# SCH_spacedrums_Altium.net
KiCad netlist of a schematic drawn in Altium Designer
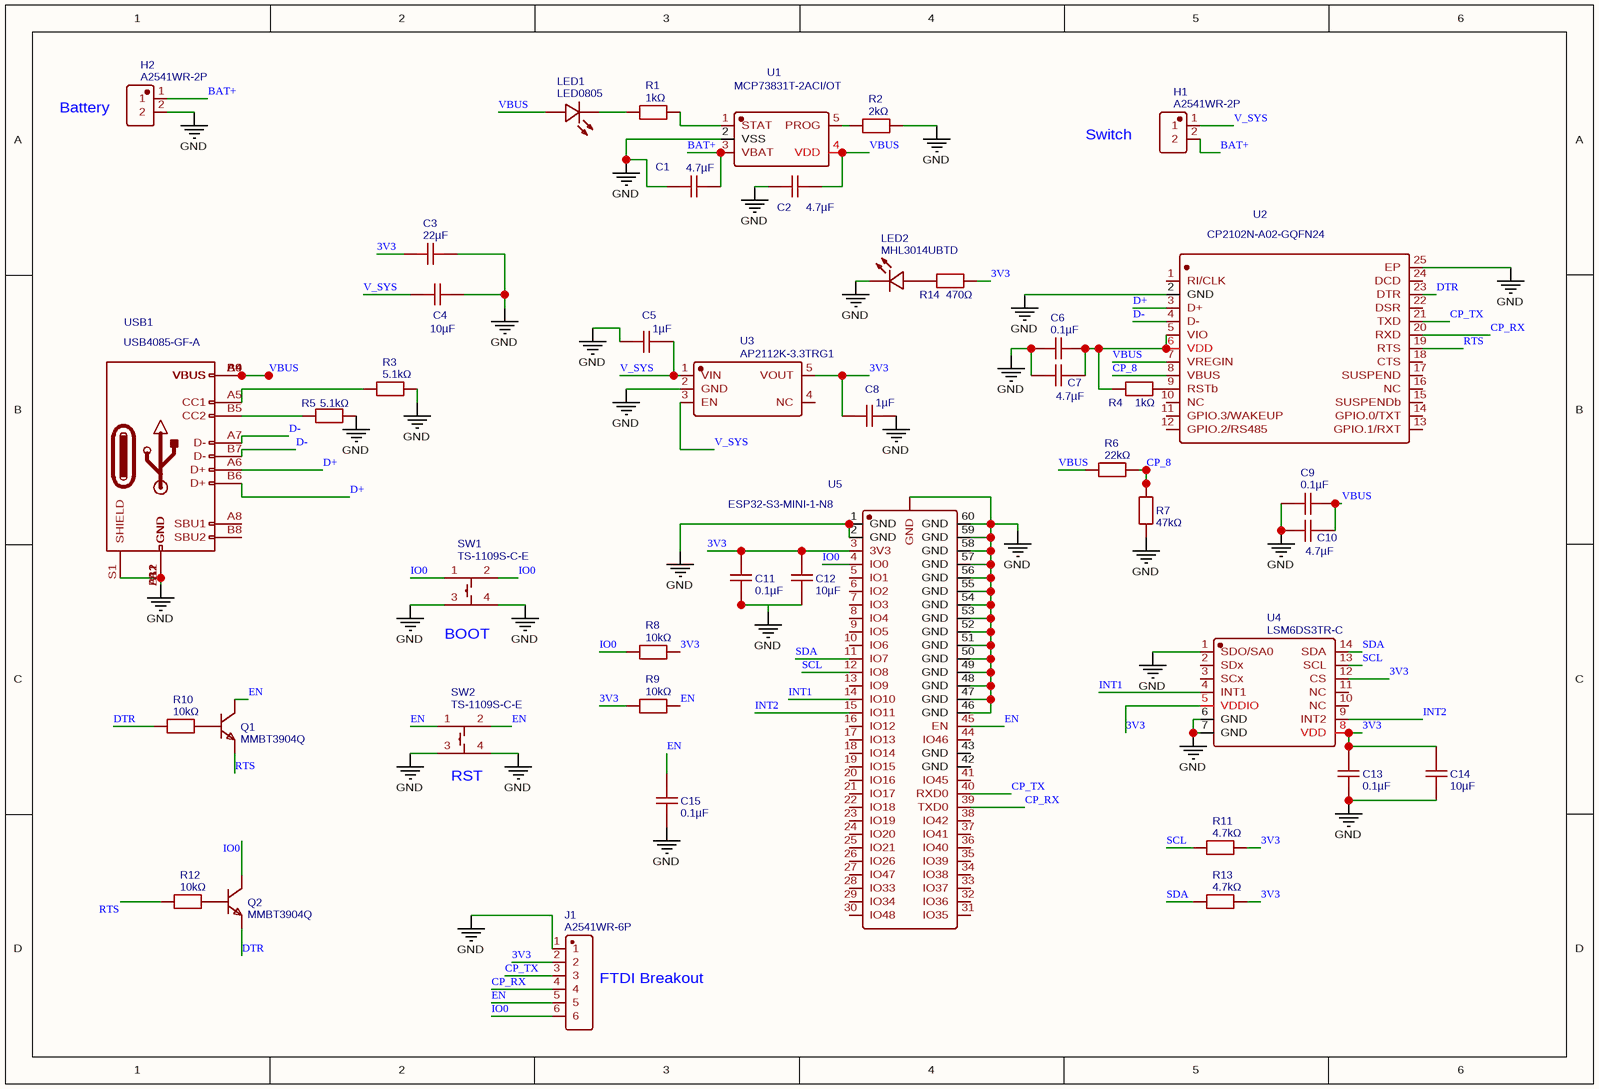
[diagram p0: SCH_spacedrums_Altium.schdoc]

(export (version "E")
  (design (tool "Eeschema 10.0.6"))
  (components
    (comp (ref "C1")
      (value "4.7µF")
      (fields
        (field (name "MANUFACTURER") "YAGEO(国巨)")
        (field (name "MANUFACTURER PART") "CC0805FRNPO0BN680")
        (field (name "CONTRIBUTOR") "lcsc")
      )
      (libsource (lib "altium-import") (part "root_0_4.7µF_"))
    )
    (comp (ref "C2")
      (value "4.7µF")
      (fields
        (field (name "MANUFACTURER") "YAGEO(国巨)")
        (field (name "MANUFACTURER PART") "CC0805FRNPO0BN680")
        (field (name "CONTRIBUTOR") "lcsc")
      )
      (libsource (lib "altium-import") (part "root_0_4.7µF_"))
    )
    (comp (ref "C3")
      (value "22µF")
      (fields
        (field (name "MANUFACTURER") "YAGEO(国巨)")
        (field (name "MANUFACTURER PART") "CC0805FRNPO0BN680")
        (field (name "CONTRIBUTOR") "lcsc")
      )
      (libsource (lib "altium-import") (part "root_0_22µF_"))
    )
    (comp (ref "C4")
      (value "10µF")
      (fields
        (field (name "MANUFACTURER") "YAGEO(国巨)")
        (field (name "MANUFACTURER PART") "CC0805FRNPO0BN680")
        (field (name "CONTRIBUTOR") "lcsc")
      )
      (libsource (lib "altium-import") (part "root_0_10µF_"))
    )
    (comp (ref "C5")
      (value "1µF")
      (fields
        (field (name "MANUFACTURER") "YAGEO(国巨)")
        (field (name "MANUFACTURER PART") "CC0805FRNPO0BN680")
        (field (name "CONTRIBUTOR") "lcsc")
      )
      (libsource (lib "altium-import") (part "root_0_1µF_"))
    )
    (comp (ref "C6")
      (value "0.1µF")
      (fields
        (field (name "MANUFACTURER") "YAGEO(国巨)")
        (field (name "MANUFACTURER PART") "CC0805FRNPO0BN680")
        (field (name "CONTRIBUTOR") "lcsc")
      )
      (libsource (lib "altium-import") (part "root_0_0.1µF_"))
    )
    (comp (ref "C7")
      (value "4.7µF")
      (fields
        (field (name "MANUFACTURER") "YAGEO(国巨)")
        (field (name "MANUFACTURER PART") "CC0805FRNPO0BN680")
        (field (name "CONTRIBUTOR") "lcsc")
      )
      (libsource (lib "altium-import") (part "root_0_4.7µF_"))
    )
    (comp (ref "C8")
      (value "1µF")
      (fields
        (field (name "MANUFACTURER") "YAGEO(国巨)")
        (field (name "MANUFACTURER PART") "CC0805FRNPO0BN680")
        (field (name "CONTRIBUTOR") "lcsc")
      )
      (libsource (lib "altium-import") (part "root_0_1µF_"))
    )
    (comp (ref "C9")
      (value "0.1µF")
      (fields
        (field (name "MANUFACTURER") "YAGEO(国巨)")
        (field (name "MANUFACTURER PART") "CC0805FRNPO0BN680")
        (field (name "CONTRIBUTOR") "lcsc")
      )
      (libsource (lib "altium-import") (part "root_0_0.1µF_"))
    )
    (comp (ref "C10")
      (value "4.7µF")
      (fields
        (field (name "MANUFACTURER") "YAGEO(国巨)")
        (field (name "MANUFACTURER PART") "CC0805FRNPO0BN680")
        (field (name "CONTRIBUTOR") "lcsc")
      )
      (libsource (lib "altium-import") (part "root_0_4.7µF_"))
    )
    (comp (ref "C11")
      (value "0.1µF")
      (fields
        (field (name "MANUFACTURER") "YAGEO(国巨)")
        (field (name "MANUFACTURER PART") "CC0805FRNPO0BN680")
        (field (name "CONTRIBUTOR") "lcsc")
      )
      (libsource (lib "altium-import") (part "root_1_0.1µF_"))
    )
    (comp (ref "C12")
      (value "10µF")
      (fields
        (field (name "MANUFACTURER") "YAGEO(国巨)")
        (field (name "MANUFACTURER PART") "CC0805FRNPO0BN680")
        (field (name "CONTRIBUTOR") "lcsc")
      )
      (libsource (lib "altium-import") (part "root_1_10µF_"))
    )
    (comp (ref "C13")
      (value "0.1µF")
      (fields
        (field (name "MANUFACTURER") "YAGEO(国巨)")
        (field (name "MANUFACTURER PART") "CC0805FRNPO0BN680")
        (field (name "CONTRIBUTOR") "lcsc")
      )
      (libsource (lib "altium-import") (part "root_1_0.1µF_"))
    )
    (comp (ref "C14")
      (value "10µF")
      (fields
        (field (name "MANUFACTURER") "YAGEO(国巨)")
        (field (name "MANUFACTURER PART") "CC0805FRNPO0BN680")
        (field (name "CONTRIBUTOR") "lcsc")
      )
      (libsource (lib "altium-import") (part "root_1_10µF_"))
    )
    (comp (ref "C15")
      (value "0.1µF")
      (fields
        (field (name "MANUFACTURER") "YAGEO(国巨)")
        (field (name "MANUFACTURER PART") "CC0805FRNPO0BN680")
        (field (name "CONTRIBUTOR") "lcsc")
      )
      (libsource (lib "altium-import") (part "root_1_0.1µF_"))
    )
    (comp (ref "H1")
      (value "A2541WR-2P")
      (fields (field (name "MANUFACTURER") "CJT(长江连接器)") (field (name "CONTRIBUTOR") "eng.mostafa2571"))
      (libsource (lib "altium-import") (part "root_0_A2541WR-2P_"))
    )
    (comp (ref "H2")
      (value "A2541WR-2P")
      (fields (field (name "MANUFACTURER") "CJT(长江连接器)") (field (name "CONTRIBUTOR") "eng.mostafa2571"))
      (libsource (lib "altium-import") (part "root_0_A2541WR-2P_"))
    )
    (comp (ref "J1")
      (value "A2541WR-6P")
      (fields (field (name "MANUFACTURER") "CJT(长江连接器)") (field (name "CONTRIBUTOR") "ARNABMACH0"))
      (libsource (lib "altium-import") (part "root_0_A2541WR-6P_"))
    )
    (comp (ref "LED1")
      (value "LED0805")
      (fields (field (name "MANUFACTURER PART") "led0805") (field (name "CONTRIBUTOR") "LCSC"))
      (libsource (lib "altium-import") (part "root_2_LED0805_"))
    )
    (comp (ref "LED2")
      (value "MHL3014UBTD")
      (fields (field (name "MANUFACTURER") "MEIHUA(美华)") (field (name "CONTRIBUTOR") "LCSC"))
      (libsource (lib "altium-import") (part "root_0_MHL3014UBTD_"))
    )
    (comp (ref "Q1")
      (value "MMBT3904Q")
      (fields (field (name "MANUFACTURER") "YANGJIE(扬杰)") (field (name "CONTRIBUTOR") "lcsc"))
      (libsource (lib "altium-import") (part "root_0_MMBT3904Q_"))
    )
    (comp (ref "Q2")
      (value "MMBT3904Q")
      (fields (field (name "MANUFACTURER") "YANGJIE(扬杰)") (field (name "CONTRIBUTOR") "lcsc"))
      (libsource (lib "altium-import") (part "root_0_MMBT3904Q_"))
    )
    (comp (ref "R1")
      (value "1kΩ")
      (fields
        (field (name "MANUFACTURER") "FOJAN(富捷)")
        (field (name "MANUFACTURER PART") "FRC0805F7873TS")
        (field (name "CONTRIBUTOR") "lcsc")
      )
      (libsource (lib "altium-import") (part "root_0_1kΩ_"))
    )
    (comp (ref "R2")
      (value "2kΩ")
      (fields
        (field (name "MANUFACTURER") "FOJAN(富捷)")
        (field (name "MANUFACTURER PART") "FRC0805F7873TS")
        (field (name "CONTRIBUTOR") "lcsc")
      )
      (libsource (lib "altium-import") (part "root_0_2kΩ_"))
    )
    (comp (ref "R3")
      (value "5.1kΩ")
      (fields
        (field (name "MANUFACTURER") "FOJAN(富捷)")
        (field (name "MANUFACTURER PART") "FRC0805F7873TS")
        (field (name "CONTRIBUTOR") "lcsc")
      )
      (libsource (lib "altium-import") (part "root_0_5.1kΩ_"))
    )
    (comp (ref "R4")
      (value "1kΩ")
      (fields
        (field (name "MANUFACTURER") "FOJAN(富捷)")
        (field (name "MANUFACTURER PART") "FRC0805F7873TS")
        (field (name "CONTRIBUTOR") "lcsc")
      )
      (libsource (lib "altium-import") (part "root_2_1kΩ_"))
    )
    (comp (ref "R5")
      (value "5.1kΩ")
      (fields
        (field (name "MANUFACTURER") "FOJAN(富捷)")
        (field (name "MANUFACTURER PART") "FRC0805F7873TS")
        (field (name "CONTRIBUTOR") "lcsc")
      )
      (libsource (lib "altium-import") (part "root_0_5.1kΩ_"))
    )
    (comp (ref "R6")
      (value "22kΩ")
      (fields
        (field (name "MANUFACTURER") "FOJAN(富捷)")
        (field (name "MANUFACTURER PART") "FRC0805F7873TS")
        (field (name "CONTRIBUTOR") "lcsc")
      )
      (libsource (lib "altium-import") (part "root_0_22kΩ_"))
    )
    (comp (ref "R7")
      (value "47kΩ")
      (fields
        (field (name "MANUFACTURER") "FOJAN(富捷)")
        (field (name "MANUFACTURER PART") "FRC0805F7873TS")
        (field (name "CONTRIBUTOR") "lcsc")
      )
      (libsource (lib "altium-import") (part "root_1_47kΩ_"))
    )
    (comp (ref "R8")
      (value "10kΩ")
      (fields
        (field (name "MANUFACTURER") "FOJAN(富捷)")
        (field (name "MANUFACTURER PART") "FRC0805F7873TS")
        (field (name "CONTRIBUTOR") "lcsc")
      )
      (libsource (lib "altium-import") (part "root_0_10kΩ_"))
    )
    (comp (ref "R9")
      (value "10kΩ")
      (fields
        (field (name "MANUFACTURER") "FOJAN(富捷)")
        (field (name "MANUFACTURER PART") "FRC0805F7873TS")
        (field (name "CONTRIBUTOR") "lcsc")
      )
      (libsource (lib "altium-import") (part "root_0_10kΩ_"))
    )
    (comp (ref "R10")
      (value "10kΩ")
      (fields
        (field (name "MANUFACTURER") "FOJAN(富捷)")
        (field (name "MANUFACTURER PART") "FRC0805F7873TS")
        (field (name "CONTRIBUTOR") "lcsc")
      )
      (libsource (lib "altium-import") (part "root_0_10kΩ_"))
    )
    (comp (ref "R11")
      (value "4.7kΩ")
      (fields
        (field (name "MANUFACTURER") "FOJAN(富捷)")
        (field (name "MANUFACTURER PART") "FRC0805F7873TS")
        (field (name "CONTRIBUTOR") "lcsc")
      )
      (libsource (lib "altium-import") (part "root_0_4.7kΩ_"))
    )
    (comp (ref "R12")
      (value "10kΩ")
      (fields
        (field (name "MANUFACTURER") "FOJAN(富捷)")
        (field (name "MANUFACTURER PART") "FRC0805F7873TS")
        (field (name "CONTRIBUTOR") "lcsc")
      )
      (libsource (lib "altium-import") (part "root_2_10kΩ_"))
    )
    (comp (ref "R13")
      (value "4.7kΩ")
      (fields
        (field (name "MANUFACTURER") "FOJAN(富捷)")
        (field (name "MANUFACTURER PART") "FRC0805F7873TS")
        (field (name "CONTRIBUTOR") "lcsc")
      )
      (libsource (lib "altium-import") (part "root_0_4.7kΩ_"))
    )
    (comp (ref "R14")
      (value "470Ω")
      (fields
        (field (name "MANUFACTURER") "FOJAN(富捷)")
        (field (name "MANUFACTURER PART") "FRC0805F7873TS")
        (field (name "CONTRIBUTOR") "lcsc")
      )
      (libsource (lib "altium-import") (part "root_2_470Ω_"))
    )
    (comp (ref "SW1")
      (value "TS-1109S-C-E")
      (fields (field (name "MANUFACTURER") "XKB Connectivity(中国星坤)") (field (name "CONTRIBUTOR") "LCSC"))
      (libsource (lib "altium-import") (part "root_0_TS-1109S-C-E_"))
    )
    (comp (ref "SW2")
      (value "TS-1109S-C-E")
      (fields (field (name "MANUFACTURER") "XKB Connectivity(中国星坤)") (field (name "CONTRIBUTOR") "LCSC"))
      (libsource (lib "altium-import") (part "root_0_TS-1109S-C-E_"))
    )
    (comp (ref "U1")
      (value "MCP73831T-2ACI/OT")
      (fields (field (name "MANUFACTURER") "MICROCHIP(美国微芯)") (field (name "CONTRIBUTOR") "LCSC"))
      (libsource (lib "altium-import") (part "root_0_MCP73831T-2ACI/OT_"))
    )
    (comp (ref "U2")
      (value "CP2102N-A02-GQFN24")
      (fields (field (name "MANUFACTURER") "SKYWORKS/SILICON LABS(芯科)") (field (name "CONTRIBUTOR") "LCSC"))
      (libsource (lib "altium-import") (part "root_0_CP2102N-A02-GQFN24_"))
    )
    (comp (ref "U3")
      (value "AP2112K-3.3TRG1")
      (fields (field (name "MANUFACTURER") "DIODES(美台)") (field (name "CONTRIBUTOR") "LCSC"))
      (libsource (lib "altium-import") (part "root_0_AP2112K-3.3TRG1_"))
    )
    (comp (ref "U4")
      (value "LSM6DS3TR-C")
      (fields (field (name "MANUFACTURER") "ST(意法半导体)") (field (name "CONTRIBUTOR") "LCSC"))
      (libsource (lib "altium-import") (part "root_0_LSM6DS3TR-C_"))
    )
    (comp (ref "U5")
      (value "ESP32-S3-MINI-1-N8")
      (fields (field (name "MANUFACTURER") "ESPRESSIF(乐鑫)") (field (name "CONTRIBUTOR") "lcsc"))
      (libsource (lib "altium-import") (part "root_0_ESP32-S3-MINI-1-N8_"))
    )
    (comp (ref "USB1")
      (value "USB4085-GF-A")
      (fields (field (name "CONTRIBUTOR") "lcsc"))
      (libsource (lib "altium-import") (part "root_0_USB4085-GF-A_"))
    )
  )
  (nets
    (net (code "1") (name "/3V3") (class "Default")
      (node (ref "C11") (pin "2") (pinfunction "2_2") (pintype "passive"))
      (node (ref "C12") (pin "2") (pinfunction "2_2") (pintype "passive"))
      (node (ref "C13") (pin "2") (pinfunction "2_2") (pintype "passive"))
      (node (ref "C14") (pin "2") (pinfunction "2_2") (pintype "passive"))
      (node (ref "C3") (pin "1") (pinfunction "1_1") (pintype "passive"))
      (node (ref "C8") (pin "1") (pinfunction "1_1") (pintype "passive"))
      (node (ref "J1") (pin "2") (pinfunction "2_2") (pintype "passive"))
      (node (ref "R11") (pin "2") (pinfunction "2_2") (pintype "passive"))
      (node (ref "R13") (pin "2") (pinfunction "2_2") (pintype "passive"))
      (node (ref "R14") (pin "1") (pinfunction "1_1") (pintype "passive"))
      (node (ref "R8") (pin "2") (pinfunction "2_2") (pintype "passive"))
      (node (ref "R9") (pin "1") (pinfunction "1_1") (pintype "passive"))
      (node (ref "U3") (pin "5") (pinfunction "VOUT_5") (pintype "passive"))
      (node (ref "U4") (pin "12") (pinfunction "CS_12") (pintype "passive"))
      (node (ref "U4") (pin "5") (pinfunction "VDDIO_5") (pintype "passive"))
      (node (ref "U4") (pin "8") (pinfunction "VDD_8") (pintype "passive"))
      (node (ref "U5") (pin "3") (pinfunction "3V3_3") (pintype "passive"))
    )
    (net (code "2") (name "/BAT+") (class "Default")
      (node (ref "C1") (pin "2") (pinfunction "2_2") (pintype "passive"))
      (node (ref "H1") (pin "2") (pinfunction "2_2") (pintype "passive"))
      (node (ref "H2") (pin "1") (pinfunction "1_1") (pintype "passive"))
      (node (ref "U1") (pin "3") (pinfunction "VBAT_3") (pintype "passive"))
    )
    (net (code "3") (name "/CP_8") (class "Default")
      (node (ref "R6") (pin "2") (pinfunction "2_2") (pintype "passive"))
      (node (ref "R7") (pin "2") (pinfunction "2_2") (pintype "passive"))
      (node (ref "U2") (pin "8") (pinfunction "VBUS_8") (pintype "passive"))
    )
    (net (code "4") (name "/CP_RX") (class "Default")
      (node (ref "J1") (pin "4") (pinfunction "4_4") (pintype "passive"))
      (node (ref "U2") (pin "20") (pinfunction "RXD_20") (pintype "passive"))
      (node (ref "U5") (pin "39") (pinfunction "TXD0_39") (pintype "passive"))
    )
    (net (code "5") (name "/CP_TX") (class "Default")
      (node (ref "J1") (pin "3") (pinfunction "3_3") (pintype "passive"))
      (node (ref "U2") (pin "21") (pinfunction "TXD_21") (pintype "passive"))
      (node (ref "U5") (pin "40") (pinfunction "RXD0_40") (pintype "passive"))
    )
    (net (code "6") (name "/D+") (class "Default")
      (node (ref "U2") (pin "3") (pinfunction "D+_3") (pintype "passive"))
      (node (ref "USB1") (pin "A6") (pinfunction "D+_A6") (pintype "passive"))
      (node (ref "USB1") (pin "B6") (pinfunction "D+_B6") (pintype "passive"))
    )
    (net (code "7") (name "/D-") (class "Default")
      (node (ref "U2") (pin "4") (pinfunction "D-_4") (pintype "passive"))
      (node (ref "USB1") (pin "A7") (pinfunction "D-_A7") (pintype "passive"))
      (node (ref "USB1") (pin "B7") (pinfunction "D-_B7") (pintype "passive"))
    )
    (net (code "8") (name "/DTR") (class "Default")
      (node (ref "Q2") (pin "2") (pinfunction "E_2") (pintype "passive"))
      (node (ref "R10") (pin "1") (pinfunction "1_1") (pintype "passive"))
      (node (ref "U2") (pin "23") (pinfunction "DTR_23") (pintype "passive"))
    )
    (net (code "9") (name "/EN") (class "Default")
      (node (ref "C15") (pin "2") (pinfunction "2_2") (pintype "passive"))
      (node (ref "J1") (pin "5") (pinfunction "5_5") (pintype "passive"))
      (node (ref "Q1") (pin "3") (pinfunction "C_3") (pintype "passive"))
      (node (ref "R9") (pin "2") (pinfunction "2_2") (pintype "passive"))
      (node (ref "SW2") (pin "1") (pinfunction "1_1") (pintype "passive"))
      (node (ref "SW2") (pin "2") (pinfunction "2_2") (pintype "passive"))
      (node (ref "U5") (pin "45") (pinfunction "EN_45") (pintype "passive"))
    )
    (net (code "10") (name "/INT1") (class "Default")
      (node (ref "U4") (pin "4") (pinfunction "INT1_4") (pintype "passive"))
      (node (ref "U5") (pin "14") (pinfunction "IO10_14") (pintype "passive"))
    )
    (net (code "11") (name "/INT2") (class "Default")
      (node (ref "U4") (pin "9") (pinfunction "INT2_9") (pintype "passive"))
      (node (ref "U5") (pin "15") (pinfunction "IO11_15") (pintype "passive"))
    )
    (net (code "12") (name "/IO0") (class "Default")
      (node (ref "J1") (pin "6") (pinfunction "6_6") (pintype "passive"))
      (node (ref "Q2") (pin "3") (pinfunction "C_3") (pintype "passive"))
      (node (ref "R8") (pin "1") (pinfunction "1_1") (pintype "passive"))
      (node (ref "SW1") (pin "1") (pinfunction "1_1") (pintype "passive"))
      (node (ref "SW1") (pin "2") (pinfunction "2_2") (pintype "passive"))
      (node (ref "U5") (pin "4") (pinfunction "IO0_4") (pintype "passive"))
    )
    (net (code "13") (name "/RTS") (class "Default")
      (node (ref "Q1") (pin "2") (pinfunction "E_2") (pintype "passive"))
      (node (ref "R12") (pin "2") (pinfunction "2_2") (pintype "passive"))
      (node (ref "U2") (pin "19") (pinfunction "RTS_19") (pintype "passive"))
    )
    (net (code "14") (name "/SCL") (class "Default")
      (node (ref "R11") (pin "1") (pinfunction "1_1") (pintype "passive"))
      (node (ref "U4") (pin "13") (pinfunction "SCL_13") (pintype "passive"))
      (node (ref "U5") (pin "12") (pinfunction "IO8_12") (pintype "passive"))
    )
    (net (code "15") (name "/SDA") (class "Default")
      (node (ref "R13") (pin "1") (pinfunction "1_1") (pintype "passive"))
      (node (ref "U4") (pin "14") (pinfunction "SDA_14") (pintype "passive"))
      (node (ref "U5") (pin "11") (pinfunction "IO7_11") (pintype "passive"))
    )
    (net (code "16") (name "/VBUS") (class "Default")
      (node (ref "C10") (pin "2") (pinfunction "2_2") (pintype "passive"))
      (node (ref "C2") (pin "2") (pinfunction "2_2") (pintype "passive"))
      (node (ref "C9") (pin "2") (pinfunction "2_2") (pintype "passive"))
      (node (ref "LED1") (pin "2") (pinfunction "+_2") (pintype "passive"))
      (node (ref "R6") (pin "1") (pinfunction "1_1") (pintype "passive"))
      (node (ref "U1") (pin "4") (pinfunction "VDD_4") (pintype "passive"))
      (node (ref "U2") (pin "7") (pinfunction "VREGIN_7") (pintype "passive"))
      (node (ref "USB1") (pin "A4") (pinfunction "VBUS_A4") (pintype "passive"))
      (node (ref "USB1") (pin "A9") (pinfunction "VBUS_A9") (pintype "passive"))
      (node (ref "USB1") (pin "B4") (pinfunction "VBUS_B4") (pintype "passive"))
      (node (ref "USB1") (pin "B9") (pinfunction "VBUS_B9") (pintype "passive"))
    )
    (net (code "17") (name "/V_SYS") (class "Default")
      (node (ref "C4") (pin "1") (pinfunction "1_1") (pintype "passive"))
      (node (ref "C5") (pin "2") (pinfunction "2_2") (pintype "passive"))
      (node (ref "H1") (pin "1") (pinfunction "1_1") (pintype "passive"))
      (node (ref "U3") (pin "1") (pinfunction "VIN_1") (pintype "passive"))
      (node (ref "U3") (pin "3") (pinfunction "EN_3") (pintype "passive"))
    )
    (net (code "18") (name "GND") (class "Default")
      (node (ref "C1") (pin "1") (pinfunction "1_1") (pintype "passive"))
      (node (ref "C10") (pin "1") (pinfunction "1_1") (pintype "passive"))
      (node (ref "C11") (pin "1") (pinfunction "1_1") (pintype "passive"))
      (node (ref "C12") (pin "1") (pinfunction "1_1") (pintype "passive"))
      (node (ref "C13") (pin "1") (pinfunction "1_1") (pintype "passive"))
      (node (ref "C14") (pin "1") (pinfunction "1_1") (pintype "passive"))
      (node (ref "C15") (pin "1") (pinfunction "1_1") (pintype "passive"))
      (node (ref "C2") (pin "1") (pinfunction "1_1") (pintype "passive"))
      (node (ref "C3") (pin "2") (pinfunction "2_2") (pintype "passive"))
      (node (ref "C4") (pin "2") (pinfunction "2_2") (pintype "passive"))
      (node (ref "C5") (pin "1") (pinfunction "1_1") (pintype "passive"))
      (node (ref "C6") (pin "1") (pinfunction "1_1") (pintype "passive"))
      (node (ref "C7") (pin "1") (pinfunction "1_1") (pintype "passive"))
      (node (ref "C8") (pin "2") (pinfunction "2_2") (pintype "passive"))
      (node (ref "C9") (pin "1") (pinfunction "1_1") (pintype "passive"))
      (node (ref "H2") (pin "2") (pinfunction "2_2") (pintype "passive"))
      (node (ref "J1") (pin "1") (pinfunction "1_1") (pintype "passive"))
      (node (ref "LED2") (pin "1") (pinfunction "-_1") (pintype "passive"))
      (node (ref "R2") (pin "2") (pinfunction "2_2") (pintype "passive"))
      (node (ref "R3") (pin "2") (pinfunction "2_2") (pintype "passive"))
      (node (ref "R5") (pin "2") (pinfunction "2_2") (pintype "passive"))
      (node (ref "R7") (pin "1") (pinfunction "1_1") (pintype "passive"))
      (node (ref "SW1") (pin "3") (pinfunction "3_3") (pintype "passive"))
      (node (ref "SW1") (pin "4") (pinfunction "4_4") (pintype "passive"))
      (node (ref "SW2") (pin "3") (pinfunction "3_3") (pintype "passive"))
      (node (ref "SW2") (pin "4") (pinfunction "4_4") (pintype "passive"))
      (node (ref "U1") (pin "2") (pinfunction "VSS_2") (pintype "passive"))
      (node (ref "U2") (pin "2") (pinfunction "GND_2") (pintype "passive"))
      (node (ref "U2") (pin "25") (pinfunction "EP_25") (pintype "passive"))
      (node (ref "U3") (pin "2") (pinfunction "GND_2") (pintype "passive"))
      (node (ref "U4") (pin "1") (pinfunction "SDO/SA0_1") (pintype "passive"))
      (node (ref "U4") (pin "6") (pinfunction "GND_6") (pintype "passive"))
      (node (ref "U4") (pin "7") (pinfunction "GND_7") (pintype "passive"))
      (node (ref "U5") (pin "1") (pinfunction "GND_1") (pintype "passive"))
      (node (ref "U5") (pin "2") (pinfunction "GND_2") (pintype "passive"))
      (node (ref "U5") (pin "46") (pinfunction "GND_46") (pintype "passive"))
      (node (ref "U5") (pin "47") (pinfunction "GND_47") (pintype "passive"))
      (node (ref "U5") (pin "48") (pinfunction "GND_48") (pintype "passive"))
      (node (ref "U5") (pin "49") (pinfunction "GND_49") (pintype "passive"))
      (node (ref "U5") (pin "50") (pinfunction "GND_50") (pintype "passive"))
      (node (ref "U5") (pin "51") (pinfunction "GND_51") (pintype "passive"))
      (node (ref "U5") (pin "52") (pinfunction "GND_52") (pintype "passive"))
      (node (ref "U5") (pin "53") (pinfunction "GND_53") (pintype "passive"))
      (node (ref "U5") (pin "54") (pinfunction "GND_54") (pintype "passive"))
      (node (ref "U5") (pin "55") (pinfunction "GND_55") (pintype "passive"))
      (node (ref "U5") (pin "56") (pinfunction "GND_56") (pintype "passive"))
      (node (ref "U5") (pin "57") (pinfunction "GND_57") (pintype "passive"))
      (node (ref "U5") (pin "58") (pinfunction "GND_58") (pintype "passive"))
      (node (ref "U5") (pin "59") (pinfunction "GND_59") (pintype "passive"))
      (node (ref "U5") (pin "60") (pinfunction "GND_60") (pintype "passive"))
      (node (ref "U5") (pin "GND") (pinfunction "GND_GND") (pintype "passive"))
      (node (ref "USB1") (pin "A1") (pinfunction "GND_A1") (pintype "passive"))
      (node (ref "USB1") (pin "A12") (pinfunction "GND_A12") (pintype "passive"))
      (node (ref "USB1") (pin "B1") (pinfunction "GND_B1") (pintype "passive"))
      (node (ref "USB1") (pin "B12") (pinfunction "GND_B12") (pintype "passive"))
      (node (ref "USB1") (pin "S1") (pinfunction "SHIELD_S1") (pintype "passive"))
    )
    (net (code "19") (name "Net-(LED1--)") (class "Default")
      (node (ref "LED1") (pin "1") (pinfunction "-_1") (pintype "passive"))
      (node (ref "R1") (pin "1") (pinfunction "1_1") (pintype "passive"))
    )
    (net (code "20") (name "Net-(LED2-+)") (class "Default")
      (node (ref "LED2") (pin "2") (pinfunction "+_2") (pintype "passive"))
      (node (ref "R14") (pin "2") (pinfunction "2_2") (pintype "passive"))
    )
    (net (code "21") (name "Net-(Q1-B)") (class "Default")
      (node (ref "Q1") (pin "1") (pinfunction "B_1") (pintype "passive"))
      (node (ref "R10") (pin "2") (pinfunction "2_2") (pintype "passive"))
    )
    (net (code "22") (name "Net-(Q2-B)") (class "Default")
      (node (ref "Q2") (pin "1") (pinfunction "B_1") (pintype "passive"))
      (node (ref "R12") (pin "1") (pinfunction "1_1") (pintype "passive"))
    )
    (net (code "23") (name "Net-(U1-PROG)") (class "Default")
      (node (ref "R2") (pin "1") (pinfunction "1_1") (pintype "passive"))
      (node (ref "U1") (pin "5") (pinfunction "PROG_5") (pintype "passive"))
    )
    (net (code "24") (name "Net-(U1-STAT)") (class "Default")
      (node (ref "R1") (pin "2") (pinfunction "2_2") (pintype "passive"))
      (node (ref "U1") (pin "1") (pinfunction "STAT_1") (pintype "passive"))
    )
    (net (code "25") (name "Net-(U2-RSTb)") (class "Default")
      (node (ref "R4") (pin "1") (pinfunction "1_1") (pintype "passive"))
      (node (ref "U2") (pin "9") (pinfunction "RSTb_9") (pintype "passive"))
    )
    (net (code "26") (name "Net-(U2-VDD)") (class "Default")
      (node (ref "C6") (pin "2") (pinfunction "2_2") (pintype "passive"))
      (node (ref "C7") (pin "2") (pinfunction "2_2") (pintype "passive"))
      (node (ref "R4") (pin "2") (pinfunction "2_2") (pintype "passive"))
      (node (ref "U2") (pin "5") (pinfunction "VIO_5") (pintype "passive"))
      (node (ref "U2") (pin "6") (pinfunction "VDD_6") (pintype "passive"))
    )
    (net (code "27") (name "Net-(USB1-CC1)") (class "Default")
      (node (ref "R3") (pin "1") (pinfunction "1_1") (pintype "passive"))
      (node (ref "USB1") (pin "A5") (pinfunction "CC1_A5") (pintype "passive"))
    )
    (net (code "28") (name "Net-(USB1-CC2)") (class "Default")
      (node (ref "R5") (pin "1") (pinfunction "1_1") (pintype "passive"))
      (node (ref "USB1") (pin "B5") (pinfunction "CC2_B5") (pintype "passive"))
    )
    (net (code "29") (name "unconnected-(U2-CTS-Pad18)") (class "Default")
      (node (ref "U2") (pin "18") (pinfunction "CTS_18") (pintype "passive"))
    )
    (net (code "30") (name "unconnected-(U2-DCD-Pad24)") (class "Default")
      (node (ref "U2") (pin "24") (pinfunction "DCD_24") (pintype "passive"))
    )
    (net (code "31") (name "unconnected-(U2-DSR-Pad22)") (class "Default")
      (node (ref "U2") (pin "22") (pinfunction "DSR_22") (pintype "passive"))
    )
    (net (code "32") (name "unconnected-(U2-GPIO.0{slash}TXT-Pad14)") (class "Default")
      (node (ref "U2") (pin "14") (pinfunction "GPIO.0/TXT_14") (pintype "passive"))
    )
    (net (code "33") (name "unconnected-(U2-GPIO.1{slash}RXT-Pad13)") (class "Default")
      (node (ref "U2") (pin "13") (pinfunction "GPIO.1/RXT_13") (pintype "passive"))
    )
    (net (code "34") (name "unconnected-(U2-GPIO.2{slash}RS485-Pad12)") (class "Default")
      (node (ref "U2") (pin "12") (pinfunction "GPIO.2/RS485_12") (pintype "passive"))
    )
    (net (code "35") (name "unconnected-(U2-GPIO.3{slash}WAKEUP-Pad11)") (class "Default")
      (node (ref "U2") (pin "11") (pinfunction "GPIO.3/WAKEUP_11") (pintype "passive"))
    )
    (net (code "36") (name "unconnected-(U2-NC-Pad10)") (class "Default")
      (node (ref "U2") (pin "10") (pinfunction "NC_10") (pintype "passive"))
    )
    (net (code "37") (name "unconnected-(U2-NC-Pad16)") (class "Default")
      (node (ref "U2") (pin "16") (pinfunction "NC_16") (pintype "passive"))
    )
    (net (code "38") (name "unconnected-(U2-RI{slash}CLK-Pad1)") (class "Default")
      (node (ref "U2") (pin "1") (pinfunction "RI/CLK_1") (pintype "passive"))
    )
    (net (code "39") (name "unconnected-(U2-SUSPEND-Pad17)") (class "Default")
      (node (ref "U2") (pin "17") (pinfunction "SUSPEND_17") (pintype "passive"))
    )
    (net (code "40") (name "unconnected-(U2-SUSPENDb-Pad15)") (class "Default")
      (node (ref "U2") (pin "15") (pinfunction "SUSPENDb_15") (pintype "passive"))
    )
    (net (code "41") (name "unconnected-(U3-NC-Pad4)") (class "Default")
      (node (ref "U3") (pin "4") (pinfunction "NC_4") (pintype "passive"))
    )
    (net (code "42") (name "unconnected-(U4-NC-Pad10)") (class "Default")
      (node (ref "U4") (pin "10") (pinfunction "NC_10") (pintype "passive"))
    )
    (net (code "43") (name "unconnected-(U4-NC-Pad11)") (class "Default")
      (node (ref "U4") (pin "11") (pinfunction "NC_11") (pintype "passive"))
    )
    (net (code "44") (name "unconnected-(U4-SCx-Pad3)") (class "Default")
      (node (ref "U4") (pin "3") (pinfunction "SCx_3") (pintype "passive"))
    )
    (net (code "45") (name "unconnected-(U4-SDx-Pad2)") (class "Default")
      (node (ref "U4") (pin "2") (pinfunction "SDx_2") (pintype "passive"))
    )
    (net (code "46") (name "unconnected-(U5-GND-Pad42)") (class "Default")
      (node (ref "U5") (pin "42") (pinfunction "GND_42") (pintype "passive"))
    )
    (net (code "47") (name "unconnected-(U5-GND-Pad43)") (class "Default")
      (node (ref "U5") (pin "43") (pinfunction "GND_43") (pintype "passive"))
    )
    (net (code "48") (name "unconnected-(U5-IO1-Pad5)") (class "Default")
      (node (ref "U5") (pin "5") (pinfunction "IO1_5") (pintype "passive"))
    )
    (net (code "49") (name "unconnected-(U5-IO2-Pad6)") (class "Default")
      (node (ref "U5") (pin "6") (pinfunction "IO2_6") (pintype "passive"))
    )
    (net (code "50") (name "unconnected-(U5-IO3-Pad7)") (class "Default")
      (node (ref "U5") (pin "7") (pinfunction "IO3_7") (pintype "passive"))
    )
    (net (code "51") (name "unconnected-(U5-IO4-Pad8)") (class "Default")
      (node (ref "U5") (pin "8") (pinfunction "IO4_8") (pintype "passive"))
    )
    (net (code "52") (name "unconnected-(U5-IO5-Pad9)") (class "Default")
      (node (ref "U5") (pin "9") (pinfunction "IO5_9") (pintype "passive"))
    )
    (net (code "53") (name "unconnected-(U5-IO6-Pad10)") (class "Default")
      (node (ref "U5") (pin "10") (pinfunction "IO6_10") (pintype "passive"))
    )
    (net (code "54") (name "unconnected-(U5-IO9-Pad13)") (class "Default")
      (node (ref "U5") (pin "13") (pinfunction "IO9_13") (pintype "passive"))
    )
    (net (code "55") (name "unconnected-(U5-IO12-Pad16)") (class "Default")
      (node (ref "U5") (pin "16") (pinfunction "IO12_16") (pintype "passive"))
    )
    (net (code "56") (name "unconnected-(U5-IO13-Pad17)") (class "Default")
      (node (ref "U5") (pin "17") (pinfunction "IO13_17") (pintype "passive"))
    )
    (net (code "57") (name "unconnected-(U5-IO14-Pad18)") (class "Default")
      (node (ref "U5") (pin "18") (pinfunction "IO14_18") (pintype "passive"))
    )
    (net (code "58") (name "unconnected-(U5-IO15-Pad19)") (class "Default")
      (node (ref "U5") (pin "19") (pinfunction "IO15_19") (pintype "passive"))
    )
    (net (code "59") (name "unconnected-(U5-IO16-Pad20)") (class "Default")
      (node (ref "U5") (pin "20") (pinfunction "IO16_20") (pintype "passive"))
    )
    (net (code "60") (name "unconnected-(U5-IO17-Pad21)") (class "Default")
      (node (ref "U5") (pin "21") (pinfunction "IO17_21") (pintype "passive"))
    )
    (net (code "61") (name "unconnected-(U5-IO18-Pad22)") (class "Default")
      (node (ref "U5") (pin "22") (pinfunction "IO18_22") (pintype "passive"))
    )
    (net (code "62") (name "unconnected-(U5-IO19-Pad23)") (class "Default")
      (node (ref "U5") (pin "23") (pinfunction "IO19_23") (pintype "passive"))
    )
    (net (code "63") (name "unconnected-(U5-IO20-Pad24)") (class "Default")
      (node (ref "U5") (pin "24") (pinfunction "IO20_24") (pintype "passive"))
    )
    (net (code "64") (name "unconnected-(U5-IO21-Pad25)") (class "Default")
      (node (ref "U5") (pin "25") (pinfunction "IO21_25") (pintype "passive"))
    )
    (net (code "65") (name "unconnected-(U5-IO26-Pad26)") (class "Default")
      (node (ref "U5") (pin "26") (pinfunction "IO26_26") (pintype "passive"))
    )
    (net (code "66") (name "unconnected-(U5-IO33-Pad28)") (class "Default")
      (node (ref "U5") (pin "28") (pinfunction "IO33_28") (pintype "passive"))
    )
    (net (code "67") (name "unconnected-(U5-IO34-Pad29)") (class "Default")
      (node (ref "U5") (pin "29") (pinfunction "IO34_29") (pintype "passive"))
    )
    (net (code "68") (name "unconnected-(U5-IO35-Pad31)") (class "Default")
      (node (ref "U5") (pin "31") (pinfunction "IO35_31") (pintype "passive"))
    )
    (net (code "69") (name "unconnected-(U5-IO36-Pad32)") (class "Default")
      (node (ref "U5") (pin "32") (pinfunction "IO36_32") (pintype "passive"))
    )
    (net (code "70") (name "unconnected-(U5-IO37-Pad33)") (class "Default")
      (node (ref "U5") (pin "33") (pinfunction "IO37_33") (pintype "passive"))
    )
    (net (code "71") (name "unconnected-(U5-IO38-Pad34)") (class "Default")
      (node (ref "U5") (pin "34") (pinfunction "IO38_34") (pintype "passive"))
    )
    (net (code "72") (name "unconnected-(U5-IO39-Pad35)") (class "Default")
      (node (ref "U5") (pin "35") (pinfunction "IO39_35") (pintype "passive"))
    )
    (net (code "73") (name "unconnected-(U5-IO40-Pad36)") (class "Default")
      (node (ref "U5") (pin "36") (pinfunction "IO40_36") (pintype "passive"))
    )
    (net (code "74") (name "unconnected-(U5-IO41-Pad37)") (class "Default")
      (node (ref "U5") (pin "37") (pinfunction "IO41_37") (pintype "passive"))
    )
    (net (code "75") (name "unconnected-(U5-IO42-Pad38)") (class "Default")
      (node (ref "U5") (pin "38") (pinfunction "IO42_38") (pintype "passive"))
    )
    (net (code "76") (name "unconnected-(U5-IO45-Pad41)") (class "Default")
      (node (ref "U5") (pin "41") (pinfunction "IO45_41") (pintype "passive"))
    )
    (net (code "77") (name "unconnected-(U5-IO46-Pad44)") (class "Default")
      (node (ref "U5") (pin "44") (pinfunction "IO46_44") (pintype "passive"))
    )
    (net (code "78") (name "unconnected-(U5-IO47-Pad27)") (class "Default")
      (node (ref "U5") (pin "27") (pinfunction "IO47_27") (pintype "passive"))
    )
    (net (code "79") (name "unconnected-(U5-IO48-Pad30)") (class "Default")
      (node (ref "U5") (pin "30") (pinfunction "IO48_30") (pintype "passive"))
    )
    (net (code "80") (name "unconnected-(USB1-SBU1-PadA8)") (class "Default")
      (node (ref "USB1") (pin "A8") (pinfunction "SBU1_A8") (pintype "passive"))
    )
    (net (code "81") (name "unconnected-(USB1-SBU2-PadB8)") (class "Default")
      (node (ref "USB1") (pin "B8") (pinfunction "SBU2_B8") (pintype "passive"))
    )
  )
)
